# power.net
KiCad netlist of a schematic drawn in Altium Designer
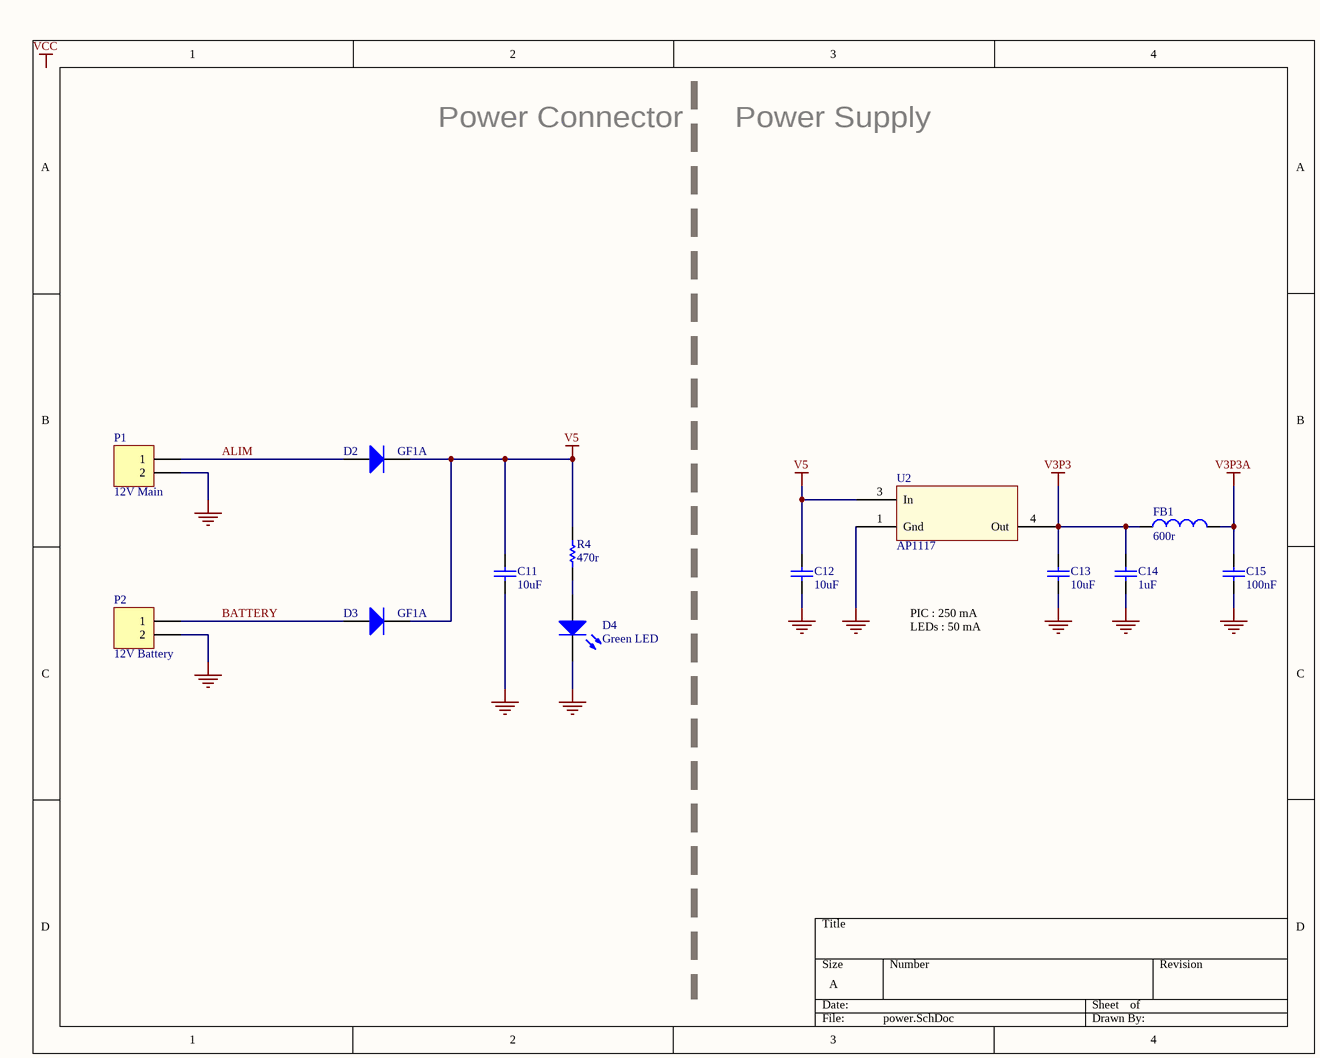
[diagram p0: power.SchDoc]

(export (version "E")
  (design (tool "Eeschema 10.0.6"))
  (components
    (comp (ref "C11")
      (value "10uF")
      (footprint "RAD-0.3")
      (description "Capacitor")
      (fields (field (name "PUBLISHER") "Altium Limited"))
      (libsource (lib "Miscellaneous Devices") (part "Cap"))
    )
    (comp (ref "C12")
      (value "10uF")
      (footprint "RAD-0.3")
      (description "Capacitor")
      (fields (field (name "PUBLISHER") "Altium Limited"))
      (libsource (lib "Miscellaneous Devices") (part "Cap"))
    )
    (comp (ref "C13")
      (value "10uF")
      (footprint "RAD-0.3")
      (description "Capacitor")
      (fields (field (name "PUBLISHER") "Altium Limited"))
      (libsource (lib "Miscellaneous Devices") (part "Cap"))
    )
    (comp (ref "C14")
      (value "1uF")
      (footprint "RAD-0.3")
      (description "Capacitor")
      (fields (field (name "PUBLISHER") "Altium Limited"))
      (libsource (lib "Miscellaneous Devices") (part "Cap"))
    )
    (comp (ref "C15")
      (value "100nF")
      (footprint "RAD-0.3")
      (description "Capacitor")
      (fields (field (name "PUBLISHER") "Altium Limited"))
      (libsource (lib "Miscellaneous Devices") (part "Cap"))
    )
    (comp (ref "D2")
      (value "GF1A")
      (footprint "SMC")
      (description "Default Diode")
      (fields (field (name "PUBLISHER") "Altium Limited"))
      (libsource (lib "Miscellaneous Devices") (part "Diode"))
    )
    (comp (ref "D3")
      (value "GF1A")
      (footprint "SMC")
      (description "Default Diode")
      (fields (field (name "PUBLISHER") "Altium Limited"))
      (libsource (lib "Miscellaneous Devices") (part "Diode"))
    )
    (comp (ref "D4")
      (value "Green LED")
      (footprint "LED-0")
      (description "Typical INFRARED GaAs LED")
      (fields (field (name "PUBLISHER") "Altium Limited"))
      (libsource (lib "Miscellaneous Devices") (part "LED0"))
    )
    (comp (ref "FB1")
      (value "600r")
      (footprint "0402-A")
      (description "Inductor")
      (fields (field (name "PUBLISHER") "Altium Limited"))
      (libsource (lib "Miscellaneous Devices") (part "Inductor"))
    )
    (comp (ref "P1")
      (value "12V Main")
      (footprint "HDR1X2")
      (description "Header, 2-Pin")
      (fields (field (name "PUBLISHER") "Altium Limited"))
      (libsource (lib "Miscellaneous Connectors") (part "Header 2"))
    )
    (comp (ref "P2")
      (value "12V Battery")
      (footprint "HDR1X2")
      (description "Header, 2-Pin")
      (fields (field (name "PUBLISHER") "Altium Limited"))
      (libsource (lib "Miscellaneous Connectors") (part "Header 2"))
    )
    (comp (ref "R4")
      (value "470r")
      (footprint "AXIAL-0.3")
      (description "Resistor")
      (fields (field (name "PUBLISHER") "Altium Limited"))
      (libsource (lib "Miscellaneous Devices") (part "Res1"))
    )
    (comp (ref "U2") (value "AP1117") (libsource (lib "TP2") (part "AP1117")))
  )
  (nets
    (net (code "1") (name "/ALIM") (class "Default")
      (node (ref "D2") (pin "1") (pinfunction "A_1") (pintype "passive"))
      (node (ref "P1") (pin "1") (pinfunction "1_1") (pintype "passive"))
    )
    (net (code "2") (name "/BATTERY") (class "Default")
      (node (ref "D3") (pin "1") (pinfunction "A_1") (pintype "passive"))
      (node (ref "P2") (pin "1") (pinfunction "1_1") (pintype "passive"))
    )
    (net (code "3") (name "GND") (class "Default")
      (node (ref "C11") (pin "1") (pinfunction "1_1") (pintype "passive"))
      (node (ref "C12") (pin "2") (pinfunction "2_2") (pintype "passive"))
      (node (ref "C13") (pin "2") (pinfunction "2_2") (pintype "passive"))
      (node (ref "C14") (pin "1") (pinfunction "1_1") (pintype "passive"))
      (node (ref "C15") (pin "1") (pinfunction "1_1") (pintype "passive"))
      (node (ref "D4") (pin "2") (pinfunction "K_2") (pintype "passive"))
      (node (ref "P1") (pin "2") (pinfunction "2_2") (pintype "passive"))
      (node (ref "P2") (pin "2") (pinfunction "2_2") (pintype "passive"))
      (node (ref "U2") (pin "1") (pinfunction "Gnd_1") (pintype "power_in"))
    )
    (net (code "4") (name "Net-(D4-A)") (class "Default")
      (node (ref "D4") (pin "1") (pinfunction "A_1") (pintype "passive"))
      (node (ref "R4") (pin "1") (pinfunction "1_1") (pintype "passive"))
    )
    (net (code "5") (name "V3P3") (class "Default")
      (node (ref "C13") (pin "1") (pinfunction "1_1") (pintype "passive"))
      (node (ref "C14") (pin "2") (pinfunction "2_2") (pintype "passive"))
      (node (ref "FB1") (pin "1") (pinfunction "1_1") (pintype "passive"))
      (node (ref "U2") (pin "4") (pinfunction "Out_4") (pintype "power_in"))
    )
    (net (code "6") (name "V3P3A") (class "Default")
      (node (ref "C15") (pin "2") (pinfunction "2_2") (pintype "passive"))
      (node (ref "FB1") (pin "2") (pinfunction "2_2") (pintype "passive"))
    )
    (net (code "7") (name "V5") (class "Default")
      (node (ref "C11") (pin "2") (pinfunction "2_2") (pintype "passive"))
      (node (ref "C12") (pin "1") (pinfunction "1_1") (pintype "passive"))
      (node (ref "D2") (pin "2") (pinfunction "K_2") (pintype "passive"))
      (node (ref "D3") (pin "2") (pinfunction "K_2") (pintype "passive"))
      (node (ref "R4") (pin "2") (pinfunction "2_2") (pintype "passive"))
      (node (ref "U2") (pin "3") (pinfunction "In_3") (pintype "power_in"))
    )
  )
)
